# usb.net
KiCad netlist of a schematic drawn in Altium Designer
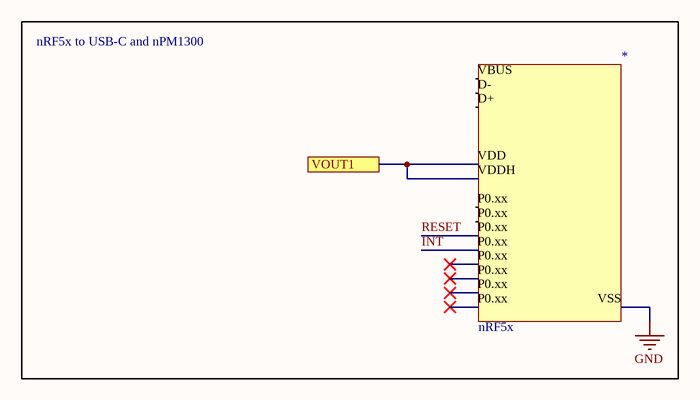
[diagram p0: usb.SchDoc]

(export (version "E")
  (design (tool "Eeschema 10.0.6"))
  (components
    (comp (ref "*")
      (value "nRF5x")
      (description "SOIC127P600X175-8N, 2 3 or 4 compatible")
      (libsource (lib "Schlib1-zasilanie") (part "nRF5x"))
    )
  )
  (nets
    (net (code "1") (name "/INT") (class "Default") (node (ref "*") (pin "P0.xx") (pintype "passive")))
    (net (code "2") (name "/RESET") (class "Default") (node (ref "*") (pin "P0.xx") (pintype "passive")))
    (net (code "3") (name "/VOUT1") (class "Default")
      (node (ref "*") (pin "VDD") (pintype "passive"))
      (node (ref "*") (pin "VDDH") (pintype "passive"))
    )
    (net (code "4") (name "GND") (class "Default") (node (ref "*") (pin "VSS") (pintype "passive")))
    (net (code "5") (name "unconnected-(*-PadD+)") (class "Default")
      (node (ref "*") (pin "D+") (pintype "passive"))
    )
    (net (code "6") (name "unconnected-(*-PadD-)") (class "Default")
      (node (ref "*") (pin "D-") (pintype "passive"))
    )
    (net (code "7") (name "unconnected-(*-PadP0.xx)") (class "Default")
      (node (ref "*") (pin "P0.xx") (pintype "passive"))
    )
    (net (code "8") (name "unconnected-(*-PadP0.xx)") (class "Default")
      (node (ref "*") (pin "P0.xx") (pintype "passive+no_connect"))
    )
    (net (code "9") (name "unconnected-(*-PadP0.xx)_1") (class "Default")
      (node (ref "*") (pin "P0.xx") (pintype "passive"))
    )
    (net (code "10") (name "unconnected-(*-PadP0.xx)_1") (class "Default")
      (node (ref "*") (pin "P0.xx") (pintype "passive+no_connect"))
    )
    (net (code "11") (name "unconnected-(*-PadP0.xx)_2") (class "Default")
      (node (ref "*") (pin "P0.xx") (pintype "passive+no_connect"))
    )
    (net (code "12") (name "unconnected-(*-PadP0.xx)_3") (class "Default")
      (node (ref "*") (pin "P0.xx") (pintype "passive+no_connect"))
    )
    (net (code "13") (name "unconnected-(*-PadVBUS)") (class "Default")
      (node (ref "*") (pin "VBUS") (pintype "passive"))
    )
  )
)
